# schematic_measure_temperature.net
KiCad netlist of a schematic drawn in EAGLE
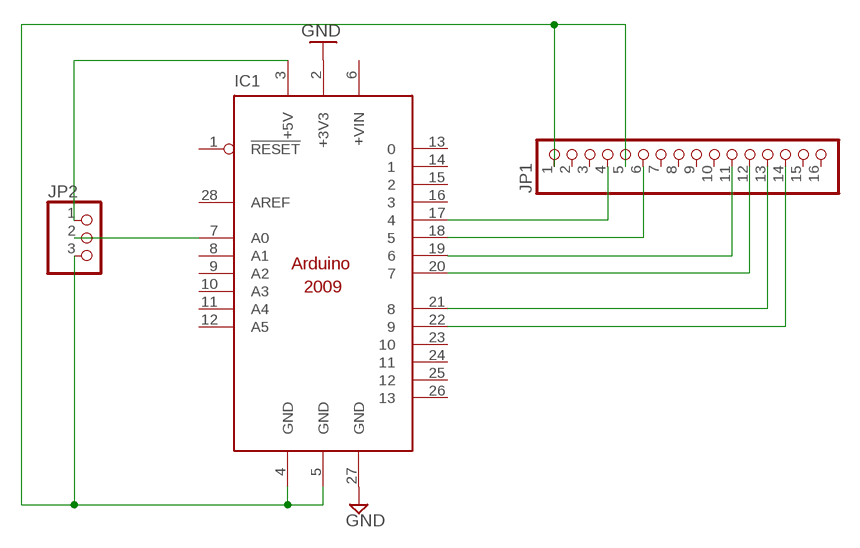
[diagram p0: schematic, sheet 1]

(export (version "E")
  (design (tool "Eeschema 10.0.6"))
  (components
    (comp (ref "IC1")
      (value "ARDUINO2009_12")
      (footprint "eagle-import:ARDUINO2009_2")
      (libsource (lib "eagle-import") (part "ARDUINO2009_12"))
    )
    (comp (ref "JP1")
      (value "PINHD-1X16")
      (footprint "eagle-import:1X16")
      (libsource (lib "eagle-import") (part "PINHD-1X16"))
    )
    (comp (ref "JP2")
      (value "PINHD-1X3")
      (footprint "eagle-import:1X03")
      (libsource (lib "eagle-import") (part "PINHD-1X3"))
    )
  )
  (nets
    (net (code "1") (name "GND") (class "Default")
      (node (ref "IC1") (pin "2") (pinfunction "+3V3_2") (pintype "power_in"))
      (node (ref "IC1") (pin "27") (pinfunction "GND_27") (pintype "power_in"))
    )
    (net (code "2") (name "Net-(IC1-+5V)") (class "Default")
      (node (ref "IC1") (pin "3") (pinfunction "+5V_3") (pintype "power_in"))
      (node (ref "JP2") (pin "1") (pinfunction "1_1") (pintype "passive"))
    )
    (net (code "3") (name "Net-(IC1-4)") (class "Default")
      (node (ref "IC1") (pin "17") (pinfunction "4_17") (pintype "bidirectional"))
      (node (ref "JP1") (pin "4") (pinfunction "4_4") (pintype "passive"))
    )
    (net (code "4") (name "Net-(IC1-5)") (class "Default")
      (node (ref "IC1") (pin "18") (pinfunction "5_18") (pintype "bidirectional"))
      (node (ref "JP1") (pin "6") (pinfunction "6_6") (pintype "passive"))
    )
    (net (code "5") (name "Net-(IC1-6)") (class "Default")
      (node (ref "IC1") (pin "19") (pinfunction "6_19") (pintype "bidirectional"))
      (node (ref "JP1") (pin "11") (pinfunction "11_11") (pintype "passive"))
    )
    (net (code "6") (name "Net-(IC1-7)") (class "Default")
      (node (ref "IC1") (pin "20") (pinfunction "7_20") (pintype "bidirectional"))
      (node (ref "JP1") (pin "12") (pinfunction "12_12") (pintype "passive"))
    )
    (net (code "7") (name "Net-(IC1-8)") (class "Default")
      (node (ref "IC1") (pin "21") (pinfunction "8_21") (pintype "bidirectional"))
      (node (ref "JP1") (pin "13") (pinfunction "13_13") (pintype "passive"))
    )
    (net (code "8") (name "Net-(IC1-9)") (class "Default")
      (node (ref "IC1") (pin "22") (pinfunction "9_22") (pintype "bidirectional"))
      (node (ref "JP1") (pin "14") (pinfunction "14_14") (pintype "passive"))
    )
    (net (code "9") (name "Net-(IC1-A0)") (class "Default")
      (node (ref "IC1") (pin "7") (pinfunction "A0_7") (pintype "bidirectional"))
      (node (ref "JP2") (pin "2") (pinfunction "2_2") (pintype "passive"))
    )
    (net (code "10") (name "Net-(IC1-GND-Pad4)") (class "Default")
      (node (ref "IC1") (pin "4") (pinfunction "GND_4") (pintype "power_in"))
      (node (ref "IC1") (pin "5") (pinfunction "GND_5") (pintype "power_in"))
      (node (ref "JP1") (pin "1") (pinfunction "1_1") (pintype "passive"))
      (node (ref "JP1") (pin "5") (pinfunction "5_5") (pintype "passive"))
      (node (ref "JP2") (pin "3") (pinfunction "3_3") (pintype "passive"))
    )
    (net (code "11") (name "unconnected-(IC1-+VIN-Pad6)") (class "Default")
      (node (ref "IC1") (pin "6") (pinfunction "+VIN_6") (pintype "bidirectional"))
    )
    (net (code "12") (name "unconnected-(IC1-0-Pad13)") (class "Default")
      (node (ref "IC1") (pin "13") (pinfunction "0_13") (pintype "bidirectional"))
    )
    (net (code "13") (name "unconnected-(IC1-1-Pad14)") (class "Default")
      (node (ref "IC1") (pin "14") (pinfunction "1_14") (pintype "bidirectional"))
    )
    (net (code "14") (name "unconnected-(IC1-2-Pad15)") (class "Default")
      (node (ref "IC1") (pin "15") (pinfunction "2_15") (pintype "bidirectional"))
    )
    (net (code "15") (name "unconnected-(IC1-3-Pad16)") (class "Default")
      (node (ref "IC1") (pin "16") (pinfunction "3_16") (pintype "bidirectional"))
    )
    (net (code "16") (name "unconnected-(IC1-10-Pad23)") (class "Default")
      (node (ref "IC1") (pin "23") (pinfunction "10_23") (pintype "bidirectional"))
    )
    (net (code "17") (name "unconnected-(IC1-11-Pad24)") (class "Default")
      (node (ref "IC1") (pin "24") (pinfunction "11_24") (pintype "bidirectional"))
    )
    (net (code "18") (name "unconnected-(IC1-12-Pad25)") (class "Default")
      (node (ref "IC1") (pin "25") (pinfunction "12_25") (pintype "bidirectional"))
    )
    (net (code "19") (name "unconnected-(IC1-13-Pad26)") (class "Default")
      (node (ref "IC1") (pin "26") (pinfunction "13_26") (pintype "bidirectional"))
    )
    (net (code "20") (name "unconnected-(IC1-A1-Pad8)") (class "Default")
      (node (ref "IC1") (pin "8") (pinfunction "A1_8") (pintype "bidirectional"))
    )
    (net (code "21") (name "unconnected-(IC1-A2-Pad9)") (class "Default")
      (node (ref "IC1") (pin "9") (pinfunction "A2_9") (pintype "bidirectional"))
    )
    (net (code "22") (name "unconnected-(IC1-A3-Pad10)") (class "Default")
      (node (ref "IC1") (pin "10") (pinfunction "A3_10") (pintype "bidirectional"))
    )
    (net (code "23") (name "unconnected-(IC1-A4-Pad11)") (class "Default")
      (node (ref "IC1") (pin "11") (pinfunction "A4_11") (pintype "bidirectional"))
    )
    (net (code "24") (name "unconnected-(IC1-A5-Pad12)") (class "Default")
      (node (ref "IC1") (pin "12") (pinfunction "A5_12") (pintype "bidirectional"))
    )
    (net (code "25") (name "unconnected-(IC1-AREF-Pad28)") (class "Default")
      (node (ref "IC1") (pin "28") (pinfunction "AREF_28") (pintype "bidirectional"))
    )
    (net (code "26") (name "unconnected-(IC1-~{RESET}-Pad1)") (class "Default")
      (node (ref "IC1") (pin "1") (pinfunction "~{RESET}_1") (pintype "bidirectional"))
    )
    (net (code "27") (name "unconnected-(JP1-Pad2)") (class "Default")
      (node (ref "JP1") (pin "2") (pinfunction "2_2") (pintype "passive"))
    )
    (net (code "28") (name "unconnected-(JP1-Pad3)") (class "Default")
      (node (ref "JP1") (pin "3") (pinfunction "3_3") (pintype "passive"))
    )
    (net (code "29") (name "unconnected-(JP1-Pad7)") (class "Default")
      (node (ref "JP1") (pin "7") (pinfunction "7_7") (pintype "passive"))
    )
    (net (code "30") (name "unconnected-(JP1-Pad8)") (class "Default")
      (node (ref "JP1") (pin "8") (pinfunction "8_8") (pintype "passive"))
    )
    (net (code "31") (name "unconnected-(JP1-Pad9)") (class "Default")
      (node (ref "JP1") (pin "9") (pinfunction "9_9") (pintype "passive"))
    )
    (net (code "32") (name "unconnected-(JP1-Pad10)") (class "Default")
      (node (ref "JP1") (pin "10") (pinfunction "10_10") (pintype "passive"))
    )
    (net (code "33") (name "unconnected-(JP1-Pad15)") (class "Default")
      (node (ref "JP1") (pin "15") (pinfunction "15_15") (pintype "passive"))
    )
    (net (code "34") (name "unconnected-(JP1-Pad16)") (class "Default")
      (node (ref "JP1") (pin "16") (pinfunction "16_16") (pintype "passive"))
    )
  )
)
